# linesensor2.net
KiCad netlist of a schematic drawn in EAGLE
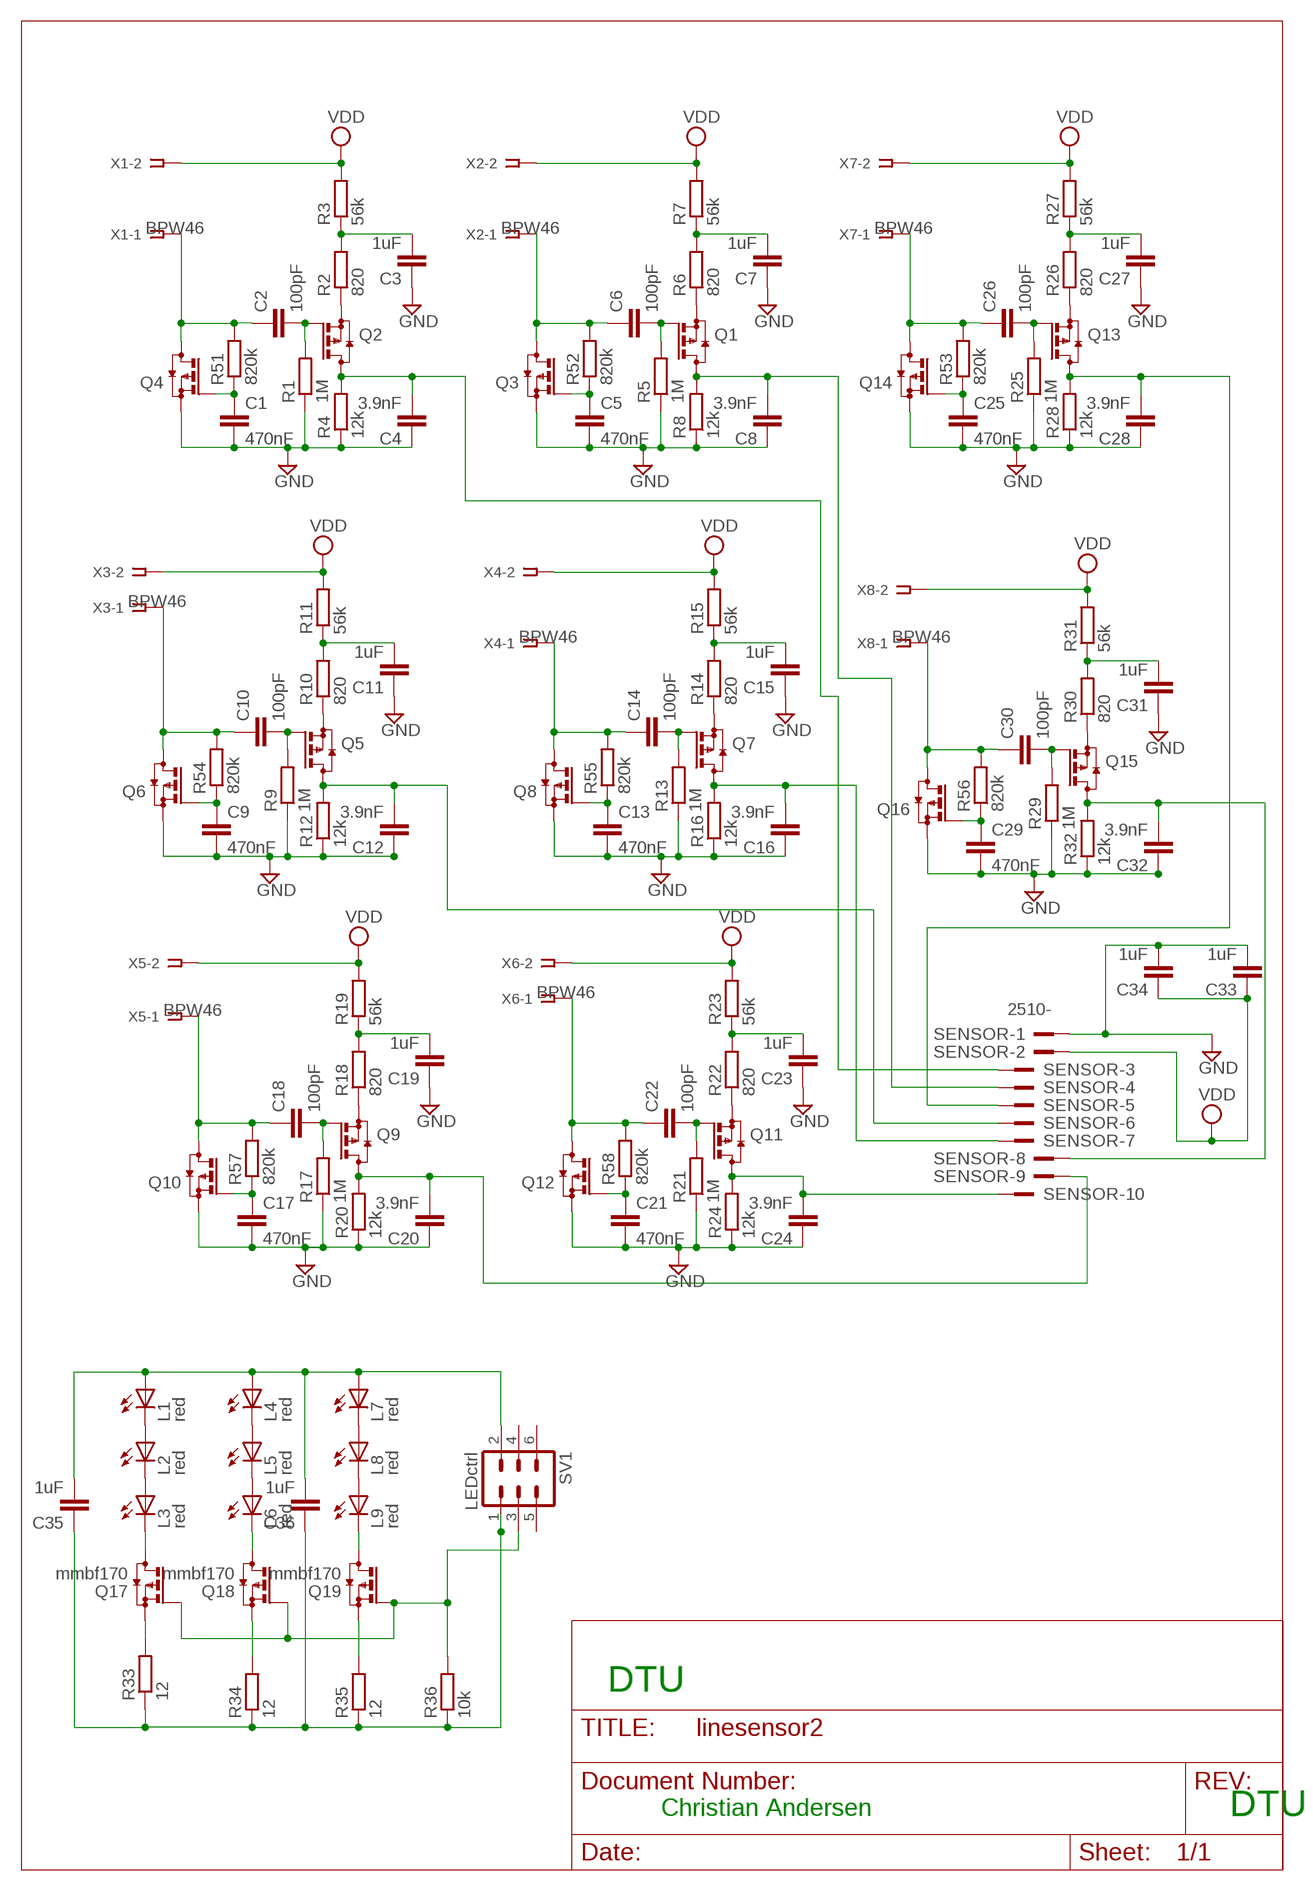
[diagram p0: schematic, sheet 1]

(export (version "E")
  (design (tool "Eeschema 10.0.6"))
  (components
    (comp (ref "C1")
      (value "470nF")
      (footprint "eagle-import:C0805")
      (libsource (lib "eagle-import") (part "C"))
    )
    (comp (ref "C2")
      (value "100pF")
      (footprint "eagle-import:C0805")
      (libsource (lib "eagle-import") (part "C"))
    )
    (comp (ref "C3")
      (value "1uF")
      (footprint "eagle-import:C0805")
      (libsource (lib "eagle-import") (part "C"))
    )
    (comp (ref "C4")
      (value "3.9nF")
      (footprint "eagle-import:C0805")
      (libsource (lib "eagle-import") (part "C"))
    )
    (comp (ref "C5")
      (value "470nF")
      (footprint "eagle-import:C0805")
      (libsource (lib "eagle-import") (part "C"))
    )
    (comp (ref "C6")
      (value "100pF")
      (footprint "eagle-import:C0805")
      (libsource (lib "eagle-import") (part "C"))
    )
    (comp (ref "C7")
      (value "1uF")
      (footprint "eagle-import:C0805")
      (libsource (lib "eagle-import") (part "C"))
    )
    (comp (ref "C8")
      (value "3.9nF")
      (footprint "eagle-import:C0805")
      (libsource (lib "eagle-import") (part "C"))
    )
    (comp (ref "C9")
      (value "470nF")
      (footprint "eagle-import:C0805")
      (libsource (lib "eagle-import") (part "C"))
    )
    (comp (ref "C10")
      (value "100pF")
      (footprint "eagle-import:C0805")
      (libsource (lib "eagle-import") (part "C"))
    )
    (comp (ref "C11")
      (value "1uF")
      (footprint "eagle-import:C0805")
      (libsource (lib "eagle-import") (part "C"))
    )
    (comp (ref "C12")
      (value "3.9nF")
      (footprint "eagle-import:C0805")
      (libsource (lib "eagle-import") (part "C"))
    )
    (comp (ref "C13")
      (value "470nF")
      (footprint "eagle-import:C0805")
      (libsource (lib "eagle-import") (part "C"))
    )
    (comp (ref "C14")
      (value "100pF")
      (footprint "eagle-import:C0805")
      (libsource (lib "eagle-import") (part "C"))
    )
    (comp (ref "C15")
      (value "1uF")
      (footprint "eagle-import:C0805")
      (libsource (lib "eagle-import") (part "C"))
    )
    (comp (ref "C16")
      (value "3.9nF")
      (footprint "eagle-import:C0805")
      (libsource (lib "eagle-import") (part "C"))
    )
    (comp (ref "C17")
      (value "470nF")
      (footprint "eagle-import:C0805")
      (libsource (lib "eagle-import") (part "C"))
    )
    (comp (ref "C18")
      (value "100pF")
      (footprint "eagle-import:C0805")
      (libsource (lib "eagle-import") (part "C"))
    )
    (comp (ref "C19")
      (value "1uF")
      (footprint "eagle-import:C0805")
      (libsource (lib "eagle-import") (part "C"))
    )
    (comp (ref "C20")
      (value "3.9nF")
      (footprint "eagle-import:C0805")
      (libsource (lib "eagle-import") (part "C"))
    )
    (comp (ref "C21")
      (value "470nF")
      (footprint "eagle-import:C0805")
      (libsource (lib "eagle-import") (part "C"))
    )
    (comp (ref "C22")
      (value "100pF")
      (footprint "eagle-import:C0805")
      (libsource (lib "eagle-import") (part "C"))
    )
    (comp (ref "C23")
      (value "1uF")
      (footprint "eagle-import:C0805")
      (libsource (lib "eagle-import") (part "C"))
    )
    (comp (ref "C24")
      (value "3.9nF")
      (footprint "eagle-import:C0805")
      (libsource (lib "eagle-import") (part "C"))
    )
    (comp (ref "C25")
      (value "470nF")
      (footprint "eagle-import:C0805")
      (libsource (lib "eagle-import") (part "C"))
    )
    (comp (ref "C26")
      (value "100pF")
      (footprint "eagle-import:C0805")
      (libsource (lib "eagle-import") (part "C"))
    )
    (comp (ref "C27")
      (value "1uF")
      (footprint "eagle-import:C0805")
      (libsource (lib "eagle-import") (part "C"))
    )
    (comp (ref "C28")
      (value "3.9nF")
      (footprint "eagle-import:C0805")
      (libsource (lib "eagle-import") (part "C"))
    )
    (comp (ref "C29")
      (value "470nF")
      (footprint "eagle-import:C0805")
      (libsource (lib "eagle-import") (part "C"))
    )
    (comp (ref "C30")
      (value "100pF")
      (footprint "eagle-import:C0805")
      (libsource (lib "eagle-import") (part "C"))
    )
    (comp (ref "C31")
      (value "1uF")
      (footprint "eagle-import:C0805")
      (libsource (lib "eagle-import") (part "C"))
    )
    (comp (ref "C32")
      (value "3.9nF")
      (footprint "eagle-import:C0805")
      (libsource (lib "eagle-import") (part "C"))
    )
    (comp (ref "C33")
      (value "1uF")
      (footprint "eagle-import:C0805")
      (libsource (lib "eagle-import") (part "C"))
    )
    (comp (ref "C34")
      (value "1uF")
      (footprint "eagle-import:C0805")
      (libsource (lib "eagle-import") (part "C"))
    )
    (comp (ref "C35")
      (value "1uF")
      (footprint "eagle-import:C0805")
      (libsource (lib "eagle-import") (part "C"))
    )
    (comp (ref "C36")
      (value "1uF")
      (footprint "eagle-import:C0805")
      (libsource (lib "eagle-import") (part "C"))
    )
    (comp (ref "L1")
      (value "red")
      (footprint "eagle-import:LED3MM")
      (libsource (lib "eagle-import") (part "LED3MM"))
    )
    (comp (ref "L2")
      (value "red")
      (footprint "eagle-import:LED3MM")
      (libsource (lib "eagle-import") (part "LED3MM"))
    )
    (comp (ref "L3")
      (value "red")
      (footprint "eagle-import:LED3MM")
      (libsource (lib "eagle-import") (part "LED3MM"))
    )
    (comp (ref "L4")
      (value "red")
      (footprint "eagle-import:LED3MM")
      (libsource (lib "eagle-import") (part "LED3MM"))
    )
    (comp (ref "L5")
      (value "red")
      (footprint "eagle-import:LED3MM")
      (libsource (lib "eagle-import") (part "LED3MM"))
    )
    (comp (ref "L6")
      (value "red")
      (footprint "eagle-import:LED3MM")
      (libsource (lib "eagle-import") (part "LED3MM"))
    )
    (comp (ref "L7")
      (value "red")
      (footprint "eagle-import:LED3MM")
      (libsource (lib "eagle-import") (part "LED3MM"))
    )
    (comp (ref "L8")
      (value "red")
      (footprint "eagle-import:LED3MM")
      (libsource (lib "eagle-import") (part "LED3MM"))
    )
    (comp (ref "L9")
      (value "red")
      (footprint "eagle-import:LED3MM")
      (libsource (lib "eagle-import") (part "LED3MM"))
    )
    (comp (ref "Q1")
      (value "BSS84")
      (footprint "eagle-import:SOT23")
      (libsource (lib "eagle-import") (part "BSS84"))
    )
    (comp (ref "Q2")
      (value "BSS84")
      (footprint "eagle-import:SOT23")
      (libsource (lib "eagle-import") (part "BSS84"))
    )
    (comp (ref "Q3")
      (value "BSS84")
      (footprint "eagle-import:SOT23")
      (libsource (lib "eagle-import") (part "BSS84"))
    )
    (comp (ref "Q4")
      (value "BSS84")
      (footprint "eagle-import:SOT23")
      (libsource (lib "eagle-import") (part "BSS84"))
    )
    (comp (ref "Q5")
      (value "BSS84")
      (footprint "eagle-import:SOT23")
      (libsource (lib "eagle-import") (part "BSS84"))
    )
    (comp (ref "Q6")
      (value "BSS84")
      (footprint "eagle-import:SOT23")
      (libsource (lib "eagle-import") (part "BSS84"))
    )
    (comp (ref "Q7")
      (value "BSS84")
      (footprint "eagle-import:SOT23")
      (libsource (lib "eagle-import") (part "BSS84"))
    )
    (comp (ref "Q8")
      (value "BSS84")
      (footprint "eagle-import:SOT23")
      (libsource (lib "eagle-import") (part "BSS84"))
    )
    (comp (ref "Q9")
      (value "BSS84")
      (footprint "eagle-import:SOT23")
      (libsource (lib "eagle-import") (part "BSS84"))
    )
    (comp (ref "Q10")
      (value "BSS84")
      (footprint "eagle-import:SOT23")
      (libsource (lib "eagle-import") (part "BSS84"))
    )
    (comp (ref "Q11")
      (value "BSS84")
      (footprint "eagle-import:SOT23")
      (libsource (lib "eagle-import") (part "BSS84"))
    )
    (comp (ref "Q12")
      (value "BSS84")
      (footprint "eagle-import:SOT23")
      (libsource (lib "eagle-import") (part "BSS84"))
    )
    (comp (ref "Q13")
      (value "BSS84")
      (footprint "eagle-import:SOT23")
      (libsource (lib "eagle-import") (part "BSS84"))
    )
    (comp (ref "Q14")
      (value "BSS84")
      (footprint "eagle-import:SOT23")
      (libsource (lib "eagle-import") (part "BSS84"))
    )
    (comp (ref "Q15")
      (value "BSS84")
      (footprint "eagle-import:SOT23")
      (libsource (lib "eagle-import") (part "BSS84"))
    )
    (comp (ref "Q16")
      (value "BSS84")
      (footprint "eagle-import:SOT23")
      (libsource (lib "eagle-import") (part "BSS84"))
    )
    (comp (ref "Q17")
      (value "mmbf170")
      (footprint "eagle-import:SOT23")
      (libsource (lib "eagle-import") (part "BSS84"))
    )
    (comp (ref "Q18")
      (value "mmbf170")
      (footprint "eagle-import:SOT23")
      (libsource (lib "eagle-import") (part "BSS84"))
    )
    (comp (ref "Q19")
      (value "mmbf170")
      (footprint "eagle-import:SOT23")
      (libsource (lib "eagle-import") (part "BSS84"))
    )
    (comp (ref "R1")
      (value "1M")
      (footprint "eagle-import:R0603")
      (libsource (lib "eagle-import") (part "RR0603"))
    )
    (comp (ref "R2")
      (value "820")
      (footprint "eagle-import:R0603")
      (libsource (lib "eagle-import") (part "RR0603"))
    )
    (comp (ref "R3")
      (value "56k")
      (footprint "eagle-import:R0603")
      (libsource (lib "eagle-import") (part "RR0603"))
    )
    (comp (ref "R4")
      (value "12k")
      (footprint "eagle-import:R0603")
      (libsource (lib "eagle-import") (part "RR0603"))
    )
    (comp (ref "R5")
      (value "1M")
      (footprint "eagle-import:R0603")
      (libsource (lib "eagle-import") (part "RR0603"))
    )
    (comp (ref "R6")
      (value "820")
      (footprint "eagle-import:R0603")
      (libsource (lib "eagle-import") (part "RR0603"))
    )
    (comp (ref "R7")
      (value "56k")
      (footprint "eagle-import:R0603")
      (libsource (lib "eagle-import") (part "RR0603"))
    )
    (comp (ref "R8")
      (value "12k")
      (footprint "eagle-import:R0603")
      (libsource (lib "eagle-import") (part "RR0603"))
    )
    (comp (ref "R9")
      (value "1M")
      (footprint "eagle-import:R0603")
      (libsource (lib "eagle-import") (part "RR0603"))
    )
    (comp (ref "R10")
      (value "820")
      (footprint "eagle-import:R0603")
      (libsource (lib "eagle-import") (part "RR0603"))
    )
    (comp (ref "R11")
      (value "56k")
      (footprint "eagle-import:R0603")
      (libsource (lib "eagle-import") (part "RR0603"))
    )
    (comp (ref "R12")
      (value "12k")
      (footprint "eagle-import:R0603")
      (libsource (lib "eagle-import") (part "RR0603"))
    )
    (comp (ref "R13")
      (value "1M")
      (footprint "eagle-import:R0603")
      (libsource (lib "eagle-import") (part "RR0603"))
    )
    (comp (ref "R14")
      (value "820")
      (footprint "eagle-import:R0603")
      (libsource (lib "eagle-import") (part "RR0603"))
    )
    (comp (ref "R15")
      (value "56k")
      (footprint "eagle-import:R0603")
      (libsource (lib "eagle-import") (part "RR0603"))
    )
    (comp (ref "R16")
      (value "12k")
      (footprint "eagle-import:R0603")
      (libsource (lib "eagle-import") (part "RR0603"))
    )
    (comp (ref "R17")
      (value "1M")
      (footprint "eagle-import:R0603")
      (libsource (lib "eagle-import") (part "RR0603"))
    )
    (comp (ref "R18")
      (value "820")
      (footprint "eagle-import:R0603")
      (libsource (lib "eagle-import") (part "RR0603"))
    )
    (comp (ref "R19")
      (value "56k")
      (footprint "eagle-import:R0603")
      (libsource (lib "eagle-import") (part "RR0603"))
    )
    (comp (ref "R20")
      (value "12k")
      (footprint "eagle-import:R0603")
      (libsource (lib "eagle-import") (part "RR0603"))
    )
    (comp (ref "R21")
      (value "1M")
      (footprint "eagle-import:R0603")
      (libsource (lib "eagle-import") (part "RR0603"))
    )
    (comp (ref "R22")
      (value "820")
      (footprint "eagle-import:R0603")
      (libsource (lib "eagle-import") (part "RR0603"))
    )
    (comp (ref "R23")
      (value "56k")
      (footprint "eagle-import:R0603")
      (libsource (lib "eagle-import") (part "RR0603"))
    )
    (comp (ref "R24")
      (value "12k")
      (footprint "eagle-import:R0603")
      (libsource (lib "eagle-import") (part "RR0603"))
    )
    (comp (ref "R25")
      (value "1M")
      (footprint "eagle-import:R0603")
      (libsource (lib "eagle-import") (part "RR0603"))
    )
    (comp (ref "R26")
      (value "820")
      (footprint "eagle-import:R0603")
      (libsource (lib "eagle-import") (part "RR0603"))
    )
    (comp (ref "R27")
      (value "56k")
      (footprint "eagle-import:R0603")
      (libsource (lib "eagle-import") (part "RR0603"))
    )
    (comp (ref "R28")
      (value "12k")
      (footprint "eagle-import:R0603")
      (libsource (lib "eagle-import") (part "RR0603"))
    )
    (comp (ref "R29")
      (value "1M")
      (footprint "eagle-import:R0603")
      (libsource (lib "eagle-import") (part "RR0603"))
    )
    (comp (ref "R30")
      (value "820")
      (footprint "eagle-import:R0603")
      (libsource (lib "eagle-import") (part "RR0603"))
    )
    (comp (ref "R31")
      (value "56k")
      (footprint "eagle-import:R0603")
      (libsource (lib "eagle-import") (part "RR0603"))
    )
    (comp (ref "R32")
      (value "12k")
      (footprint "eagle-import:R0603")
      (libsource (lib "eagle-import") (part "RR0603"))
    )
    (comp (ref "R33")
      (value "12")
      (footprint "eagle-import:R0603")
      (libsource (lib "eagle-import") (part "RR0603"))
    )
    (comp (ref "R34")
      (value "12")
      (footprint "eagle-import:R0603")
      (libsource (lib "eagle-import") (part "RR0603"))
    )
    (comp (ref "R35")
      (value "12")
      (footprint "eagle-import:R0603")
      (libsource (lib "eagle-import") (part "RR0603"))
    )
    (comp (ref "R36")
      (value "10k")
      (footprint "eagle-import:R0603")
      (libsource (lib "eagle-import") (part "RR0603"))
    )
    (comp (ref "R51")
      (value "820k")
      (footprint "eagle-import:R0603")
      (libsource (lib "eagle-import") (part "RR0603"))
    )
    (comp (ref "R52")
      (value "820k")
      (footprint "eagle-import:R0603")
      (libsource (lib "eagle-import") (part "RR0603"))
    )
    (comp (ref "R53")
      (value "820k")
      (footprint "eagle-import:R0603")
      (libsource (lib "eagle-import") (part "RR0603"))
    )
    (comp (ref "R54")
      (value "820k")
      (footprint "eagle-import:R0603")
      (libsource (lib "eagle-import") (part "RR0603"))
    )
    (comp (ref "R55")
      (value "820k")
      (footprint "eagle-import:R0603")
      (libsource (lib "eagle-import") (part "RR0603"))
    )
    (comp (ref "R56")
      (value "820k")
      (footprint "eagle-import:R0603")
      (libsource (lib "eagle-import") (part "RR0603"))
    )
    (comp (ref "R57")
      (value "820k")
      (footprint "eagle-import:R0603")
      (libsource (lib "eagle-import") (part "RR0603"))
    )
    (comp (ref "R58")
      (value "820k")
      (footprint "eagle-import:R0603")
      (libsource (lib "eagle-import") (part "RR0603"))
    )
    (comp (ref "SENSOR")
      (value "2510-")
      (footprint "eagle-import:PAK100_2500-10")
      (fields (field (name "MF") "3M") (field (name "MPN") "2510-6002UB"))
      (libsource (lib "eagle-import") (part "2510-"))
    )
    (comp (ref "SV1")
      (value "LEDctrl")
      (footprint "eagle-import:MA03-2")
      (libsource (lib "eagle-import") (part "MA03-2"))
    )
    (comp (ref "X1")
      (value "SSW-102-02-S-S-RA")
      (footprint "eagle-import:SSW-102-02-S-S-RA")
      (fields (field (name "MPN") "SSW-102-02-S-S-RA") (field (name "MPN_1") "BPW46"))
      (libsource (lib "eagle-import") (part "SSW-102-02-S-S-RA"))
    )
    (comp (ref "X2")
      (value "SSW-102-02-S-S-RA")
      (footprint "eagle-import:SSW-102-02-S-S-RA")
      (fields (field (name "MPN") "SSW-102-02-S-S-RA") (field (name "MPN_1") "BPW46"))
      (libsource (lib "eagle-import") (part "SSW-102-02-S-S-RA"))
    )
    (comp (ref "X3")
      (value "SSW-102-02-S-S-RA")
      (footprint "eagle-import:SSW-102-02-S-S-RA")
      (fields (field (name "MPN") "SSW-102-02-S-S-RA") (field (name "MPN_1") "BPW46"))
      (libsource (lib "eagle-import") (part "SSW-102-02-S-S-RA"))
    )
    (comp (ref "X4")
      (value "SSW-102-02-S-S-RA")
      (footprint "eagle-import:SSW-102-02-S-S-RA")
      (fields (field (name "MPN") "SSW-102-02-S-S-RA") (field (name "MPN_1") "BPW46"))
      (libsource (lib "eagle-import") (part "SSW-102-02-S-S-RA"))
    )
    (comp (ref "X5")
      (value "SSW-102-02-S-S-RA")
      (footprint "eagle-import:SSW-102-02-S-S-RA")
      (fields (field (name "MPN") "SSW-102-02-S-S-RA") (field (name "MPN_1") "BPW46"))
      (libsource (lib "eagle-import") (part "SSW-102-02-S-S-RA"))
    )
    (comp (ref "X6")
      (value "SSW-102-02-S-S-RA")
      (footprint "eagle-import:SSW-102-02-S-S-RA")
      (fields (field (name "MPN") "SSW-102-02-S-S-RA") (field (name "MPN_1") "BPW46"))
      (libsource (lib "eagle-import") (part "SSW-102-02-S-S-RA"))
    )
    (comp (ref "X7")
      (value "SSW-102-02-S-S-RA")
      (footprint "eagle-import:SSW-102-02-S-S-RA")
      (fields (field (name "MPN") "SSW-102-02-S-S-RA") (field (name "MPN_1") "BPW46"))
      (libsource (lib "eagle-import") (part "SSW-102-02-S-S-RA"))
    )
    (comp (ref "X8")
      (value "SSW-102-02-S-S-RA")
      (footprint "eagle-import:SSW-102-02-S-S-RA")
      (fields (field (name "MPN") "SSW-102-02-S-S-RA") (field (name "MPN_1") "BPW46"))
      (libsource (lib "eagle-import") (part "SSW-102-02-S-S-RA"))
    )
  )
  (nets
    (net (code "1") (name "GND") (class "Default")
      (node (ref "C1") (pin "2") (pinfunction "2_2") (pintype "passive"))
      (node (ref "C11") (pin "1") (pinfunction "1_1") (pintype "passive"))
      (node (ref "C12") (pin "1") (pinfunction "1_1") (pintype "passive"))
      (node (ref "C13") (pin "2") (pinfunction "2_2") (pintype "passive"))
      (node (ref "C15") (pin "1") (pinfunction "1_1") (pintype "passive"))
      (node (ref "C16") (pin "1") (pinfunction "1_1") (pintype "passive"))
      (node (ref "C17") (pin "2") (pinfunction "2_2") (pintype "passive"))
      (node (ref "C19") (pin "1") (pinfunction "1_1") (pintype "passive"))
      (node (ref "C20") (pin "1") (pinfunction "1_1") (pintype "passive"))
      (node (ref "C21") (pin "2") (pinfunction "2_2") (pintype "passive"))
      (node (ref "C23") (pin "1") (pinfunction "1_1") (pintype "passive"))
      (node (ref "C24") (pin "1") (pinfunction "1_1") (pintype "passive"))
      (node (ref "C25") (pin "2") (pinfunction "2_2") (pintype "passive"))
      (node (ref "C27") (pin "1") (pinfunction "1_1") (pintype "passive"))
      (node (ref "C28") (pin "1") (pinfunction "1_1") (pintype "passive"))
      (node (ref "C29") (pin "2") (pinfunction "2_2") (pintype "passive"))
      (node (ref "C3") (pin "1") (pinfunction "1_1") (pintype "passive"))
      (node (ref "C31") (pin "1") (pinfunction "1_1") (pintype "passive"))
      (node (ref "C32") (pin "1") (pinfunction "1_1") (pintype "passive"))
      (node (ref "C33") (pin "2") (pinfunction "2_2") (pintype "passive"))
      (node (ref "C34") (pin "2") (pinfunction "2_2") (pintype "passive"))
      (node (ref "C4") (pin "1") (pinfunction "1_1") (pintype "passive"))
      (node (ref "C5") (pin "2") (pinfunction "2_2") (pintype "passive"))
      (node (ref "C7") (pin "1") (pinfunction "1_1") (pintype "passive"))
      (node (ref "C8") (pin "1") (pinfunction "1_1") (pintype "passive"))
      (node (ref "C9") (pin "2") (pinfunction "2_2") (pintype "passive"))
      (node (ref "Q10") (pin "2") (pinfunction "S_2") (pintype "passive"))
      (node (ref "Q12") (pin "2") (pinfunction "S_2") (pintype "passive"))
      (node (ref "Q14") (pin "2") (pinfunction "S_2") (pintype "passive"))
      (node (ref "Q16") (pin "2") (pinfunction "S_2") (pintype "passive"))
      (node (ref "Q3") (pin "2") (pinfunction "S_2") (pintype "passive"))
      (node (ref "Q4") (pin "2") (pinfunction "S_2") (pintype "passive"))
      (node (ref "Q6") (pin "2") (pinfunction "S_2") (pintype "passive"))
      (node (ref "Q8") (pin "2") (pinfunction "S_2") (pintype "passive"))
      (node (ref "R1") (pin "1") (pinfunction "1_1") (pintype "passive"))
      (node (ref "R12") (pin "1") (pinfunction "1_1") (pintype "passive"))
      (node (ref "R13") (pin "1") (pinfunction "1_1") (pintype "passive"))
      (node (ref "R16") (pin "1") (pinfunction "1_1") (pintype "passive"))
      (node (ref "R17") (pin "1") (pinfunction "1_1") (pintype "passive"))
      (node (ref "R20") (pin "1") (pinfunction "1_1") (pintype "passive"))
      (node (ref "R21") (pin "1") (pinfunction "1_1") (pintype "passive"))
      (node (ref "R24") (pin "1") (pinfunction "1_1") (pintype "passive"))
      (node (ref "R25") (pin "1") (pinfunction "1_1") (pintype "passive"))
      (node (ref "R28") (pin "1") (pinfunction "1_1") (pintype "passive"))
      (node (ref "R29") (pin "1") (pinfunction "1_1") (pintype "passive"))
      (node (ref "R32") (pin "1") (pinfunction "1_1") (pintype "passive"))
      (node (ref "R4") (pin "1") (pinfunction "1_1") (pintype "passive"))
      (node (ref "R5") (pin "1") (pinfunction "1_1") (pintype "passive"))
      (node (ref "R8") (pin "1") (pinfunction "1_1") (pintype "passive"))
      (node (ref "R9") (pin "1") (pinfunction "1_1") (pintype "passive"))
      (node (ref "SENSOR") (pin "1") (pinfunction "KL_1") (pintype "passive"))
    )
    (net (code "2") (name "Net-(C3-Pad2)") (class "Default")
      (node (ref "C3") (pin "2") (pinfunction "2_2") (pintype "passive"))
      (node (ref "R2") (pin "2") (pinfunction "2_2") (pintype "passive"))
      (node (ref "R3") (pin "1") (pinfunction "1_1") (pintype "passive"))
    )
    (net (code "3") (name "Net-(C7-Pad2)") (class "Default")
      (node (ref "C7") (pin "2") (pinfunction "2_2") (pintype "passive"))
      (node (ref "R6") (pin "2") (pinfunction "2_2") (pintype "passive"))
      (node (ref "R7") (pin "1") (pinfunction "1_1") (pintype "passive"))
    )
    (net (code "4") (name "Net-(C11-Pad2)") (class "Default")
      (node (ref "C11") (pin "2") (pinfunction "2_2") (pintype "passive"))
      (node (ref "R10") (pin "2") (pinfunction "2_2") (pintype "passive"))
      (node (ref "R11") (pin "1") (pinfunction "1_1") (pintype "passive"))
    )
    (net (code "5") (name "Net-(C15-Pad2)") (class "Default")
      (node (ref "C15") (pin "2") (pinfunction "2_2") (pintype "passive"))
      (node (ref "R14") (pin "2") (pinfunction "2_2") (pintype "passive"))
      (node (ref "R15") (pin "1") (pinfunction "1_1") (pintype "passive"))
    )
    (net (code "6") (name "Net-(C19-Pad2)") (class "Default")
      (node (ref "C19") (pin "2") (pinfunction "2_2") (pintype "passive"))
      (node (ref "R18") (pin "2") (pinfunction "2_2") (pintype "passive"))
      (node (ref "R19") (pin "1") (pinfunction "1_1") (pintype "passive"))
    )
    (net (code "7") (name "Net-(C23-Pad2)") (class "Default")
      (node (ref "C23") (pin "2") (pinfunction "2_2") (pintype "passive"))
      (node (ref "R22") (pin "2") (pinfunction "2_2") (pintype "passive"))
      (node (ref "R23") (pin "1") (pinfunction "1_1") (pintype "passive"))
    )
    (net (code "8") (name "Net-(C27-Pad2)") (class "Default")
      (node (ref "C27") (pin "2") (pinfunction "2_2") (pintype "passive"))
      (node (ref "R26") (pin "2") (pinfunction "2_2") (pintype "passive"))
      (node (ref "R27") (pin "1") (pinfunction "1_1") (pintype "passive"))
    )
    (net (code "9") (name "Net-(C31-Pad2)") (class "Default")
      (node (ref "C31") (pin "2") (pinfunction "2_2") (pintype "passive"))
      (node (ref "R30") (pin "2") (pinfunction "2_2") (pintype "passive"))
      (node (ref "R31") (pin "1") (pinfunction "1_1") (pintype "passive"))
    )
    (net (code "10") (name "Net-(C35-Pad1)") (class "Default")
      (node (ref "C35") (pin "1") (pinfunction "1_1") (pintype "passive"))
      (node (ref "C36") (pin "1") (pinfunction "1_1") (pintype "passive"))
      (node (ref "R33") (pin "1") (pinfunction "1_1") (pintype "passive"))
      (node (ref "R34") (pin "1") (pinfunction "1_1") (pintype "passive"))
      (node (ref "R35") (pin "1") (pinfunction "1_1") (pintype "passive"))
      (node (ref "R36") (pin "1") (pinfunction "1_1") (pintype "passive"))
      (node (ref "SV1") (pin "1") (pinfunction "1_1") (pintype "passive"))
    )
    (net (code "11") (name "Net-(C35-Pad2)") (class "Default")
      (node (ref "C35") (pin "2") (pinfunction "2_2") (pintype "passive"))
      (node (ref "C36") (pin "2") (pinfunction "2_2") (pintype "passive"))
      (node (ref "L1") (pin "A") (pinfunction "A_A") (pintype "passive"))
      (node (ref "L4") (pin "A") (pinfunction "A_A") (pintype "passive"))
      (node (ref "L7") (pin "A") (pinfunction "A_A") (pintype "passive"))
      (node (ref "SV1") (pin "2") (pinfunction "2_2") (pintype "passive"))
    )
    (net (code "12") (name "Net-(L1-C)") (class "Default")
      (node (ref "L1") (pin "K") (pinfunction "C_K") (pintype "passive"))
      (node (ref "L2") (pin "A") (pinfunction "A_A") (pintype "passive"))
    )
    (net (code "13") (name "Net-(L2-C)") (class "Default")
      (node (ref "L2") (pin "K") (pinfunction "C_K") (pintype "passive"))
      (node (ref "L3") (pin "A") (pinfunction "A_A") (pintype "passive"))
    )
    (net (code "14") (name "Net-(L3-C)") (class "Default")
      (node (ref "L3") (pin "K") (pinfunction "C_K") (pintype "passive"))
      (node (ref "Q17") (pin "3") (pinfunction "D_3") (pintype "passive"))
    )
    (net (code "15") (name "Net-(L4-C)") (class "Default")
      (node (ref "L4") (pin "K") (pinfunction "C_K") (pintype "passive"))
      (node (ref "L5") (pin "A") (pinfunction "A_A") (pintype "passive"))
    )
    (net (code "16") (name "Net-(L5-C)") (class "Default")
      (node (ref "L5") (pin "K") (pinfunction "C_K") (pintype "passive"))
      (node (ref "L6") (pin "A") (pinfunction "A_A") (pintype "passive"))
    )
    (net (code "17") (name "Net-(L6-C)") (class "Default")
      (node (ref "L6") (pin "K") (pinfunction "C_K") (pintype "passive"))
      (node (ref "Q18") (pin "3") (pinfunction "D_3") (pintype "passive"))
    )
    (net (code "18") (name "Net-(L7-C)") (class "Default")
      (node (ref "L7") (pin "K") (pinfunction "C_K") (pintype "passive"))
      (node (ref "L8") (pin "A") (pinfunction "A_A") (pintype "passive"))
    )
    (net (code "19") (name "Net-(L8-C)") (class "Default")
      (node (ref "L8") (pin "K") (pinfunction "C_K") (pintype "passive"))
      (node (ref "L9") (pin "A") (pinfunction "A_A") (pintype "passive"))
    )
    (net (code "20") (name "Net-(L9-C)") (class "Default")
      (node (ref "L9") (pin "K") (pinfunction "C_K") (pintype "passive"))
      (node (ref "Q19") (pin "3") (pinfunction "D_3") (pintype "passive"))
    )
    (net (code "21") (name "Net-(Q1-D)") (class "Default")
      (node (ref "C8") (pin "2") (pinfunction "2_2") (pintype "passive"))
      (node (ref "Q1") (pin "3") (pinfunction "D_3") (pintype "passive"))
      (node (ref "R8") (pin "2") (pinfunction "2_2") (pintype "passive"))
      (node (ref "SENSOR") (pin "4") (pinfunction "KL_4") (pintype "passive"))
    )
    (net (code "22") (name "Net-(Q1-G)") (class "Default")
      (node (ref "C6") (pin "2") (pinfunction "2_2") (pintype "passive"))
      (node (ref "Q1") (pin "1") (pinfunction "G_1") (pintype "passive"))
      (node (ref "R5") (pin "2") (pinfunction "2_2") (pintype "passive"))
    )
    (net (code "23") (name "Net-(Q1-S)") (class "Default")
      (node (ref "Q1") (pin "2") (pinfunction "S_2") (pintype "passive"))
      (node (ref "R6") (pin "1") (pinfunction "1_1") (pintype "passive"))
    )
    (net (code "24") (name "Net-(Q2-D)") (class "Default")
      (node (ref "C4") (pin "2") (pinfunction "2_2") (pintype "passive"))
      (node (ref "Q2") (pin "3") (pinfunction "D_3") (pintype "passive"))
      (node (ref "R4") (pin "2") (pinfunction "2_2") (pintype "passive"))
      (node (ref "SENSOR") (pin "3") (pinfunction "KL_3") (pintype "passive"))
    )
    (net (code "25") (name "Net-(Q2-G)") (class "Default")
      (node (ref "C2") (pin "2") (pinfunction "2_2") (pintype "passive"))
      (node (ref "Q2") (pin "1") (pinfunction "G_1") (pintype "passive"))
      (node (ref "R1") (pin "2") (pinfunction "2_2") (pintype "passive"))
    )
    (net (code "26") (name "Net-(Q2-S)") (class "Default")
      (node (ref "Q2") (pin "2") (pinfunction "S_2") (pintype "passive"))
      (node (ref "R2") (pin "1") (pinfunction "1_1") (pintype "passive"))
    )
    (net (code "27") (name "Net-(Q3-D)") (class "Default")
      (node (ref "C6") (pin "1") (pinfunction "1_1") (pintype "passive"))
      (node (ref "Q3") (pin "3") (pinfunction "D_3") (pintype "passive"))
      (node (ref "R52") (pin "2") (pinfunction "2_2") (pintype "passive"))
      (node (ref "X2") (pin "1") (pinfunction "1_1") (pintype "passive"))
    )
    (net (code "28") (name "Net-(Q3-G)") (class "Default")
      (node (ref "C5") (pin "1") (pinfunction "1_1") (pintype "passive"))
      (node (ref "Q3") (pin "1") (pinfunction "G_1") (pintype "passive"))
      (node (ref "R52") (pin "1") (pinfunction "1_1") (pintype "passive"))
    )
    (net (code "29") (name "Net-(Q4-D)") (class "Default")
      (node (ref "C2") (pin "1") (pinfunction "1_1") (pintype "passive"))
      (node (ref "Q4") (pin "3") (pinfunction "D_3") (pintype "passive"))
      (node (ref "R51") (pin "2") (pinfunction "2_2") (pintype "passive"))
      (node (ref "X1") (pin "1") (pinfunction "1_1") (pintype "passive"))
    )
    (net (code "30") (name "Net-(Q4-G)") (class "Default")
      (node (ref "C1") (pin "1") (pinfunction "1_1") (pintype "passive"))
      (node (ref "Q4") (pin "1") (pinfunction "G_1") (pintype "passive"))
      (node (ref "R51") (pin "1") (pinfunction "1_1") (pintype "passive"))
    )
    (net (code "31") (name "Net-(Q5-D)") (class "Default")
      (node (ref "C12") (pin "2") (pinfunction "2_2") (pintype "passive"))
      (node (ref "Q5") (pin "3") (pinfunction "D_3") (pintype "passive"))
      (node (ref "R12") (pin "2") (pinfunction "2_2") (pintype "passive"))
      (node (ref "SENSOR") (pin "6") (pinfunction "KL_6") (pintype "passive"))
    )
    (net (code "32") (name "Net-(Q5-G)") (class "Default")
      (node (ref "C10") (pin "2") (pinfunction "2_2") (pintype "passive"))
      (node (ref "Q5") (pin "1") (pinfunction "G_1") (pintype "passive"))
      (node (ref "R9") (pin "2") (pinfunction "2_2") (pintype "passive"))
    )
    (net (code "33") (name "Net-(Q5-S)") (class "Default")
      (node (ref "Q5") (pin "2") (pinfunction "S_2") (pintype "passive"))
      (node (ref "R10") (pin "1") (pinfunction "1_1") (pintype "passive"))
    )
    (net (code "34") (name "Net-(Q6-D)") (class "Default")
      (node (ref "C10") (pin "1") (pinfunction "1_1") (pintype "passive"))
      (node (ref "Q6") (pin "3") (pinfunction "D_3") (pintype "passive"))
      (node (ref "R54") (pin "2") (pinfunction "2_2") (pintype "passive"))
      (node (ref "X3") (pin "1") (pinfunction "1_1") (pintype "passive"))
    )
    (net (code "35") (name "Net-(Q6-G)") (class "Default")
      (node (ref "C9") (pin "1") (pinfunction "1_1") (pintype "passive"))
      (node (ref "Q6") (pin "1") (pinfunction "G_1") (pintype "passive"))
      (node (ref "R54") (pin "1") (pinfunction "1_1") (pintype "passive"))
    )
    (net (code "36") (name "Net-(Q7-D)") (class "Default")
      (node (ref "C16") (pin "2") (pinfunction "2_2") (pintype "passive"))
      (node (ref "Q7") (pin "3") (pinfunction "D_3") (pintype "passive"))
      (node (ref "R16") (pin "2") (pinfunction "2_2") (pintype "passive"))
      (node (ref "SENSOR") (pin "7") (pinfunction "KL_7") (pintype "passive"))
    )
    (net (code "37") (name "Net-(Q7-G)") (class "Default")
      (node (ref "C14") (pin "2") (pinfunction "2_2") (pintype "passive"))
      (node (ref "Q7") (pin "1") (pinfunction "G_1") (pintype "passive"))
      (node (ref "R13") (pin "2") (pinfunction "2_2") (pintype "passive"))
    )
    (net (code "38") (name "Net-(Q7-S)") (class "Default")
      (node (ref "Q7") (pin "2") (pinfunction "S_2") (pintype "passive"))
      (node (ref "R14") (pin "1") (pinfunction "1_1") (pintype "passive"))
    )
    (net (code "39") (name "Net-(Q8-D)") (class "Default")
      (node (ref "C14") (pin "1") (pinfunction "1_1") (pintype "passive"))
      (node (ref "Q8") (pin "3") (pinfunction "D_3") (pintype "passive"))
      (node (ref "R55") (pin "2") (pinfunction "2_2") (pintype "passive"))
      (node (ref "X4") (pin "1") (pinfunction "1_1") (pintype "passive"))
    )
    (net (code "40") (name "Net-(Q8-G)") (class "Default")
      (node (ref "C13") (pin "1") (pinfunction "1_1") (pintype "passive"))
      (node (ref "Q8") (pin "1") (pinfunction "G_1") (pintype "passive"))
      (node (ref "R55") (pin "1") (pinfunction "1_1") (pintype "passive"))
    )
    (net (code "41") (name "Net-(Q9-D)") (class "Default")
      (node (ref "C20") (pin "2") (pinfunction "2_2") (pintype "passive"))
      (node (ref "Q9") (pin "3") (pinfunction "D_3") (pintype "passive"))
      (node (ref "R20") (pin "2") (pinfunction "2_2") (pintype "passive"))
      (node (ref "SENSOR") (pin "9") (pinfunction "KL_9") (pintype "passive"))
    )
    (net (code "42") (name "Net-(Q9-G)") (class "Default")
      (node (ref "C18") (pin "2") (pinfunction "2_2") (pintype "passive"))
      (node (ref "Q9") (pin "1") (pinfunction "G_1") (pintype "passive"))
      (node (ref "R17") (pin "2") (pinfunction "2_2") (pintype "passive"))
    )
    (net (code "43") (name "Net-(Q9-S)") (class "Default")
      (node (ref "Q9") (pin "2") (pinfunction "S_2") (pintype "passive"))
      (node (ref "R18") (pin "1") (pinfunction "1_1") (pintype "passive"))
    )
    (net (code "44") (name "Net-(Q10-D)") (class "Default")
      (node (ref "C18") (pin "1") (pinfunction "1_1") (pintype "passive"))
      (node (ref "Q10") (pin "3") (pinfunction "D_3") (pintype "passive"))
      (node (ref "R57") (pin "2") (pinfunction "2_2") (pintype "passive"))
      (node (ref "X5") (pin "1") (pinfunction "1_1") (pintype "passive"))
    )
    (net (code "45") (name "Net-(Q10-G)") (class "Default")
      (node (ref "C17") (pin "1") (pinfunction "1_1") (pintype "passive"))
      (node (ref "Q10") (pin "1") (pinfunction "G_1") (pintype "passive"))
      (node (ref "R57") (pin "1") (pinfunction "1_1") (pintype "passive"))
    )
    (net (code "46") (name "Net-(Q11-D)") (class "Default")
      (node (ref "C24") (pin "2") (pinfunction "2_2") (pintype "passive"))
      (node (ref "Q11") (pin "3") (pinfunction "D_3") (pintype "passive"))
      (node (ref "R24") (pin "2") (pinfunction "2_2") (pintype "passive"))
      (node (ref "SENSOR") (pin "10") (pinfunction "KL_10") (pintype "passive"))
    )
    (net (code "47") (name "Net-(Q11-G)") (class "Default")
      (node (ref "C22") (pin "2") (pinfunction "2_2") (pintype "passive"))
      (node (ref "Q11") (pin "1") (pinfunction "G_1") (pintype "passive"))
      (node (ref "R21") (pin "2") (pinfunction "2_2") (pintype "passive"))
    )
    (net (code "48") (name "Net-(Q11-S)") (class "Default")
      (node (ref "Q11") (pin "2") (pinfunction "S_2") (pintype "passive"))
      (node (ref "R22") (pin "1") (pinfunction "1_1") (pintype "passive"))
    )
    (net (code "49") (name "Net-(Q12-D)") (class "Default")
      (node (ref "C22") (pin "1") (pinfunction "1_1") (pintype "passive"))
      (node (ref "Q12") (pin "3") (pinfunction "D_3") (pintype "passive"))
      (node (ref "R58") (pin "2") (pinfunction "2_2") (pintype "passive"))
      (node (ref "X6") (pin "1") (pinfunction "1_1") (pintype "passive"))
    )
    (net (code "50") (name "Net-(Q12-G)") (class "Default")
      (node (ref "C21") (pin "1") (pinfunction "1_1") (pintype "passive"))
      (node (ref "Q12") (pin "1") (pinfunction "G_1") (pintype "passive"))
      (node (ref "R58") (pin "1") (pinfunction "1_1") (pintype "passive"))
    )
    (net (code "51") (name "Net-(Q13-D)") (class "Default")
      (node (ref "C28") (pin "2") (pinfunction "2_2") (pintype "passive"))
      (node (ref "Q13") (pin "3") (pinfunction "D_3") (pintype "passive"))
      (node (ref "R28") (pin "2") (pinfunction "2_2") (pintype "passive"))
      (node (ref "SENSOR") (pin "5") (pinfunction "KL_5") (pintype "passive"))
    )
    (net (code "52") (name "Net-(Q13-G)") (class "Default")
      (node (ref "C26") (pin "2") (pinfunction "2_2") (pintype "passive"))
      (node (ref "Q13") (pin "1") (pinfunction "G_1") (pintype "passive"))
      (node (ref "R25") (pin "2") (pinfunction "2_2") (pintype "passive"))
    )
    (net (code "53") (name "Net-(Q13-S)") (class "Default")
      (node (ref "Q13") (pin "2") (pinfunction "S_2") (pintype "passive"))
      (node (ref "R26") (pin "1") (pinfunction "1_1") (pintype "passive"))
    )
    (net (code "54") (name "Net-(Q14-D)") (class "Default")
      (node (ref "C26") (pin "1") (pinfunction "1_1") (pintype "passive"))
      (node (ref "Q14") (pin "3") (pinfunction "D_3") (pintype "passive"))
      (node (ref "R53") (pin "2") (pinfunction "2_2") (pintype "passive"))
      (node (ref "X7") (pin "1") (pinfunction "1_1") (pintype "passive"))
    )
    (net (code "55") (name "Net-(Q14-G)") (class "Default")
      (node (ref "C25") (pin "1") (pinfunction "1_1") (pintype "passive"))
      (node (ref "Q14") (pin "1") (pinfunction "G_1") (pintype "passive"))
      (node (ref "R53") (pin "1") (pinfunction "1_1") (pintype "passive"))
    )
    (net (code "56") (name "Net-(Q15-D)") (class "Default")
      (node (ref "C32") (pin "2") (pinfunction "2_2") (pintype "passive"))
      (node (ref "Q15") (pin "3") (pinfunction "D_3") (pintype "passive"))
      (node (ref "R32") (pin "2") (pinfunction "2_2") (pintype "passive"))
      (node (ref "SENSOR") (pin "8") (pinfunction "KL_8") (pintype "passive"))
    )
    (net (code "57") (name "Net-(Q15-G)") (class "Default")
      (node (ref "C30") (pin "2") (pinfunction "2_2") (pintype "passive"))
      (node (ref "Q15") (pin "1") (pinfunction "G_1") (pintype "passive"))
      (node (ref "R29") (pin "2") (pinfunction "2_2") (pintype "passive"))
    )
    (net (code "58") (name "Net-(Q15-S)") (class "Default")
      (node (ref "Q15") (pin "2") (pinfunction "S_2") (pintype "passive"))
      (node (ref "R30") (pin "1") (pinfunction "1_1") (pintype "passive"))
    )
    (net (code "59") (name "Net-(Q16-D)") (class "Default")
      (node (ref "C30") (pin "1") (pinfunction "1_1") (pintype "passive"))
      (node (ref "Q16") (pin "3") (pinfunction "D_3") (pintype "passive"))
      (node (ref "R56") (pin "2") (pinfunction "2_2") (pintype "passive"))
      (node (ref "X8") (pin "1") (pinfunction "1_1") (pintype "passive"))
    )
    (net (code "60") (name "Net-(Q16-G)") (class "Default")
      (node (ref "C29") (pin "1") (pinfunction "1_1") (pintype "passive"))
      (node (ref "Q16") (pin "1") (pinfunction "G_1") (pintype "passive"))
      (node (ref "R56") (pin "1") (pinfunction "1_1") (pintype "passive"))
    )
    (net (code "61") (name "Net-(Q17-G)") (class "Default")
      (node (ref "Q17") (pin "1") (pinfunction "G_1") (pintype "passive"))
      (node (ref "Q18") (pin "1") (pinfunction "G_1") (pintype "passive"))
      (node (ref "Q19") (pin "1") (pinfunction "G_1") (pintype "passive"))
      (node (ref "R36") (pin "2") (pinfunction "2_2") (pintype "passive"))
      (node (ref "SV1") (pin "3") (pinfunction "3_3") (pintype "passive"))
    )
    (net (code "62") (name "Net-(Q17-S)") (class "Default")
      (node (ref "Q17") (pin "2") (pinfunction "S_2") (pintype "passive"))
      (node (ref "R33") (pin "2") (pinfunction "2_2") (pintype "passive"))
    )
    (net (code "63") (name "Net-(Q18-S)") (class "Default")
      (node (ref "Q18") (pin "2") (pinfunction "S_2") (pintype "passive"))
      (node (ref "R34") (pin "2") (pinfunction "2_2") (pintype "passive"))
    )
    (net (code "64") (name "Net-(Q19-S)") (class "Default")
      (node (ref "Q19") (pin "2") (pinfunction "S_2") (pintype "passive"))
      (node (ref "R35") (pin "2") (pinfunction "2_2") (pintype "passive"))
    )
    (net (code "65") (name "VDD") (class "Default")
      (node (ref "C33") (pin "1") (pinfunction "1_1") (pintype "passive"))
      (node (ref "C34") (pin "1") (pinfunction "1_1") (pintype "passive"))
      (node (ref "R11") (pin "2") (pinfunction "2_2") (pintype "passive"))
      (node (ref "R15") (pin "2") (pinfunction "2_2") (pintype "passive"))
      (node (ref "R19") (pin "2") (pinfunction "2_2") (pintype "passive"))
      (node (ref "R23") (pin "2") (pinfunction "2_2") (pintype "passive"))
      (node (ref "R27") (pin "2") (pinfunction "2_2") (pintype "passive"))
      (node (ref "R3") (pin "2") (pinfunction "2_2") (pintype "passive"))
      (node (ref "R31") (pin "2") (pinfunction "2_2") (pintype "passive"))
      (node (ref "R7") (pin "2") (pinfunction "2_2") (pintype "passive"))
      (node (ref "SENSOR") (pin "2") (pinfunction "KL_2") (pintype "passive"))
      (node (ref "X1") (pin "2") (pinfunction "1_2") (pintype "passive"))
      (node (ref "X2") (pin "2") (pinfunction "1_2") (pintype "passive"))
      (node (ref "X3") (pin "2") (pinfunction "1_2") (pintype "passive"))
      (node (ref "X4") (pin "2") (pinfunction "1_2") (pintype "passive"))
      (node (ref "X5") (pin "2") (pinfunction "1_2") (pintype "passive"))
      (node (ref "X6") (pin "2") (pinfunction "1_2") (pintype "passive"))
      (node (ref "X7") (pin "2") (pinfunction "1_2") (pintype "passive"))
      (node (ref "X8") (pin "2") (pinfunction "1_2") (pintype "passive"))
    )
    (net (code "66") (name "unconnected-(SV1-Pad4)") (class "Default")
      (node (ref "SV1") (pin "4") (pinfunction "4_4") (pintype "passive"))
    )
    (net (code "67") (name "unconnected-(SV1-Pad5)") (class "Default")
      (node (ref "SV1") (pin "5") (pinfunction "5_5") (pintype "passive"))
    )
    (net (code "68") (name "unconnected-(SV1-Pad6)") (class "Default")
      (node (ref "SV1") (pin "6") (pinfunction "6_6") (pintype "passive"))
    )
  )
)
